# PCB.net
KiCad netlist of a schematic drawn in EAGLE
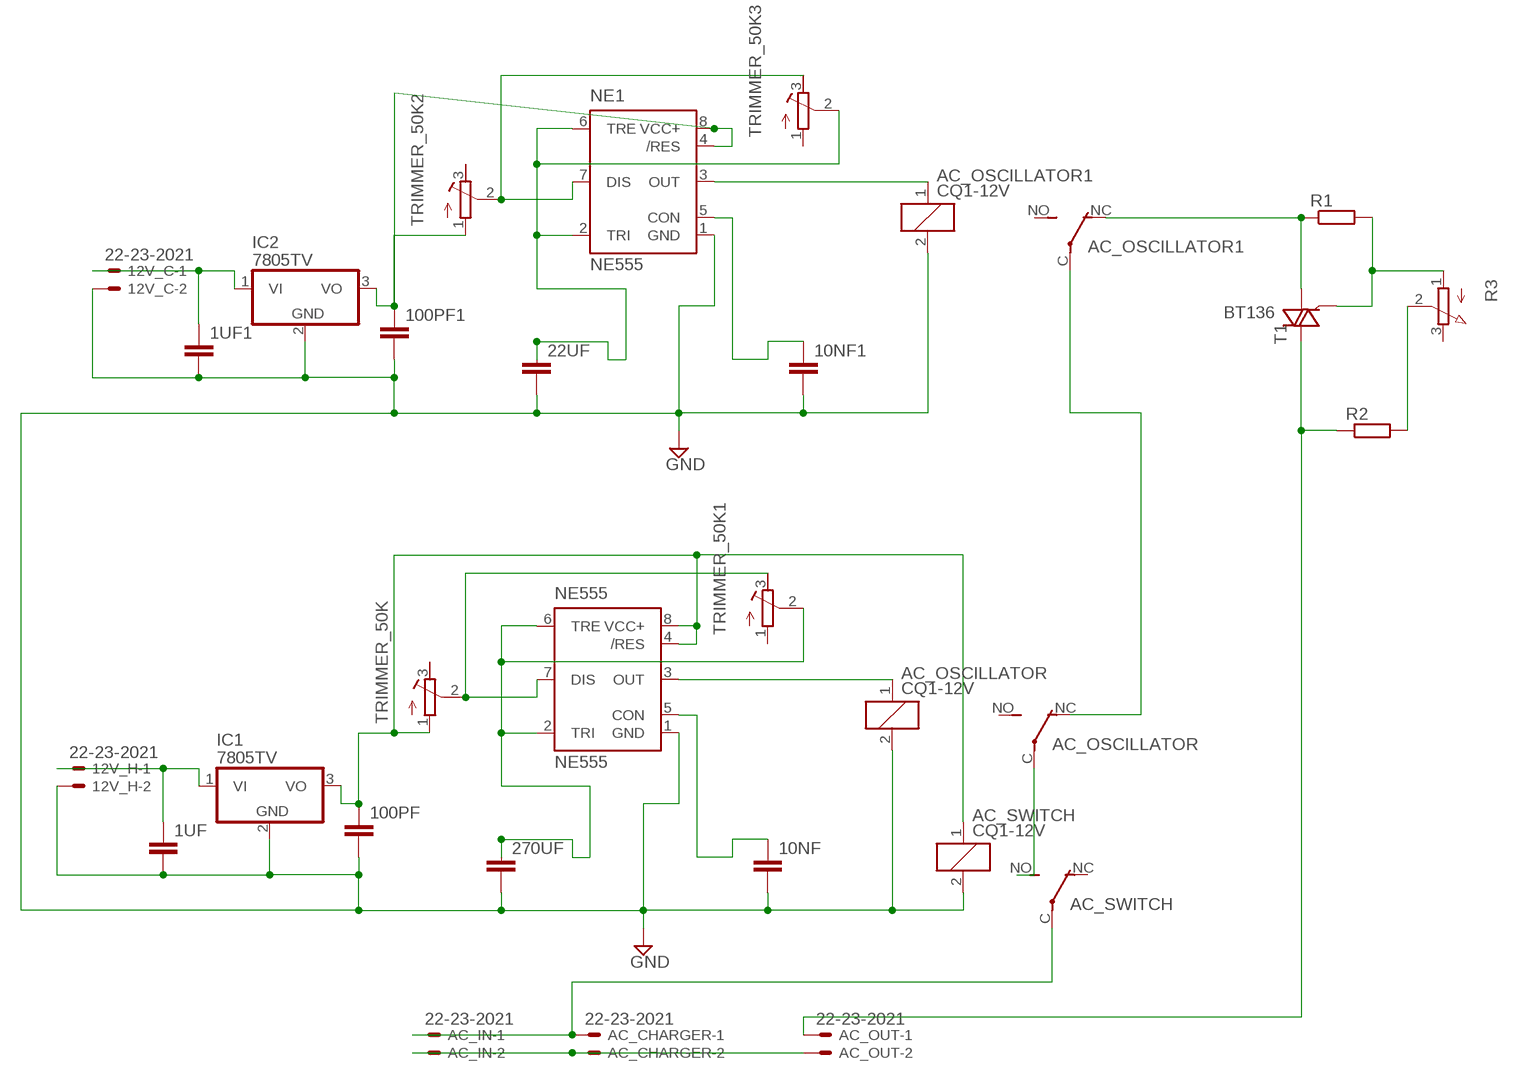
[diagram p0: schematic, sheet 1]

(export (version "E")
  (design (tool "Eeschema 10.0.6"))
  (components
    (comp (ref "1UF")
      (value "C7.5/3")
      (footprint "eagle-import:C7.5B3")
      (libsource (lib "eagle-import") (part "C7.5/3"))
    )
    (comp (ref "1UF1")
      (value "C7.5/3")
      (footprint "eagle-import:C7.5B3")
      (libsource (lib "eagle-import") (part "C7.5/3"))
    )
    (comp (ref "10NF")
      (value "C7.5/3")
      (footprint "eagle-import:C7.5B3")
      (libsource (lib "eagle-import") (part "C7.5/3"))
    )
    (comp (ref "10NF1")
      (value "C7.5/3")
      (footprint "eagle-import:C7.5B3")
      (libsource (lib "eagle-import") (part "C7.5/3"))
    )
    (comp (ref "12V_C")
      (value "22-23-2021")
      (footprint "eagle-import:22-23-2021")
      (fields (field (name "MF") "MOLEX"))
      (libsource (lib "eagle-import") (part "22-23-2021"))
    )
    (comp (ref "12V_H")
      (value "22-23-2021")
      (footprint "eagle-import:22-23-2021")
      (fields (field (name "MF") "MOLEX"))
      (libsource (lib "eagle-import") (part "22-23-2021"))
    )
    (comp (ref "22UF")
      (value "C7.5/3")
      (footprint "eagle-import:C7.5B3")
      (libsource (lib "eagle-import") (part "C7.5/3"))
    )
    (comp (ref "100PF")
      (value "C7.5/3")
      (footprint "eagle-import:C7.5B3")
      (libsource (lib "eagle-import") (part "C7.5/3"))
    )
    (comp (ref "100PF1")
      (value "C7.5/3")
      (footprint "eagle-import:C7.5B3")
      (libsource (lib "eagle-import") (part "C7.5/3"))
    )
    (comp (ref "270UF")
      (value "C7.5/3")
      (footprint "eagle-import:C7.5B3")
      (libsource (lib "eagle-import") (part "C7.5/3"))
    )
    (comp (ref "AC_CHARGER")
      (value "22-23-2021")
      (footprint "eagle-import:22-23-2021")
      (fields (field (name "MF") "MOLEX"))
      (libsource (lib "eagle-import") (part "22-23-2021"))
    )
    (comp (ref "AC_IN")
      (value "22-23-2021")
      (footprint "eagle-import:22-23-2021")
      (fields (field (name "MF") "MOLEX"))
      (libsource (lib "eagle-import") (part "22-23-2021"))
    )
    (comp (ref "AC_OSCILLATOR")
      (value "CQ1-12V")
      (footprint "eagle-import:CQ1")
      (libsource (lib "eagle-import") (part "CQ1-12V"))
    )
    (comp (ref "AC_OSCILLATOR1")
      (value "CQ1-12V")
      (footprint "eagle-import:CQ1")
      (libsource (lib "eagle-import") (part "CQ1-12V"))
    )
    (comp (ref "AC_OUT")
      (value "22-23-2021")
      (footprint "eagle-import:22-23-2021")
      (fields (field (name "MF") "MOLEX"))
      (libsource (lib "eagle-import") (part "22-23-2021"))
    )
    (comp (ref "AC_SWITCH")
      (value "CQ1-12V")
      (footprint "eagle-import:CQ1")
      (libsource (lib "eagle-import") (part "CQ1-12V"))
    )
    (comp (ref "IC1")
      (value "7805TV")
      (footprint "eagle-import:TO220V")
      (libsource (lib "eagle-import") (part "78TV05"))
    )
    (comp (ref "IC2")
      (value "7805TV")
      (footprint "eagle-import:TO220V")
      (libsource (lib "eagle-import") (part "78TV05"))
    )
    (comp (ref "NE1")
      (value "NE555")
      (footprint "eagle-import:DIL-08")
      (fields (field (name "MF") "Arrow Electronics") (field (name "MPN") "NE555N"))
      (libsource (lib "eagle-import") (part "NE555"))
    )
    (comp (ref "NE555")
      (value "NE555")
      (footprint "eagle-import:DIL-08")
      (fields (field (name "MF") "Arrow Electronics") (field (name "MPN") "NE555N"))
      (libsource (lib "eagle-import") (part "NE555"))
    )
    (comp (ref "R1")
      (value "R-EU_0204/7")
      (footprint "eagle-import:0204_7")
      (libsource (lib "eagle-import") (part "R-EU_0204/7"))
    )
    (comp (ref "R2")
      (value "R-EU_0204/7")
      (footprint "eagle-import:0204_7")
      (libsource (lib "eagle-import") (part "R-EU_0204/7"))
    )
    (comp (ref "R3")
      (value "3RP/1610N")
      (footprint "eagle-import:3RP_1610N")
      (libsource (lib "eagle-import") (part "3RP/1610N"))
    )
    (comp (ref "T1")
      (value "BT136")
      (footprint "eagle-import:TO220AB")
      (libsource (lib "eagle-import") (part "BT136"))
    )
    (comp (ref "TRIMMER_50K")
      (value "R-TRIMM64W")
      (footprint "eagle-import:RTRIM64W")
      (libsource (lib "eagle-import") (part "R-TRIMM64W"))
    )
    (comp (ref "TRIMMER_50K1")
      (value "R-TRIMM64W")
      (footprint "eagle-import:RTRIM64W")
      (libsource (lib "eagle-import") (part "R-TRIMM64W"))
    )
    (comp (ref "TRIMMER_50K2")
      (value "R-TRIMM64W")
      (footprint "eagle-import:RTRIM64W")
      (libsource (lib "eagle-import") (part "R-TRIMM64W"))
    )
    (comp (ref "TRIMMER_50K3")
      (value "R-TRIMM64W")
      (footprint "eagle-import:RTRIM64W")
      (libsource (lib "eagle-import") (part "R-TRIMM64W"))
    )
  )
  (nets
    (net (code "1") (name "GND") (class "Default")
      (node (ref "100PF") (pin "2") (pinfunction "2_2") (pintype "passive"))
      (node (ref "100PF1") (pin "2") (pinfunction "2_2") (pintype "passive"))
      (node (ref "10NF") (pin "2") (pinfunction "2_2") (pintype "passive"))
      (node (ref "10NF1") (pin "2") (pinfunction "2_2") (pintype "passive"))
      (node (ref "12V_C") (pin "2") (pinfunction "S_2") (pintype "passive"))
      (node (ref "12V_H") (pin "2") (pinfunction "S_2") (pintype "passive"))
      (node (ref "1UF") (pin "2") (pinfunction "2_2") (pintype "passive"))
      (node (ref "1UF1") (pin "2") (pinfunction "2_2") (pintype "passive"))
      (node (ref "22UF") (pin "2") (pinfunction "2_2") (pintype "passive"))
      (node (ref "270UF") (pin "2") (pinfunction "2_2") (pintype "passive"))
      (node (ref "AC_OSCILLATOR") (pin "2") (pinfunction "2_2") (pintype "passive"))
      (node (ref "AC_OSCILLATOR1") (pin "2") (pinfunction "2_2") (pintype "passive"))
      (node (ref "AC_SWITCH") (pin "2") (pinfunction "2_2") (pintype "passive"))
      (node (ref "IC1") (pin "2") (pinfunction "GND_2") (pintype "passive"))
      (node (ref "IC2") (pin "2") (pinfunction "GND_2") (pintype "passive"))
      (node (ref "NE1") (pin "1") (pinfunction "GND_1") (pintype "power_in"))
      (node (ref "NE555") (pin "1") (pinfunction "GND_1") (pintype "power_in"))
    )
    (net (code "2") (name "Net-(12V_CA-S)") (class "Default")
      (node (ref "12V_C") (pin "1") (pinfunction "S_1") (pintype "passive"))
      (node (ref "1UF1") (pin "1") (pinfunction "1_1") (pintype "passive"))
      (node (ref "IC2") (pin "1") (pinfunction "VI_1") (pintype "input"))
    )
    (net (code "3") (name "Net-(12V_HA-S)") (class "Default")
      (node (ref "12V_H") (pin "1") (pinfunction "S_1") (pintype "passive"))
      (node (ref "1UF") (pin "1") (pinfunction "1_1") (pintype "passive"))
      (node (ref "IC1") (pin "1") (pinfunction "VI_1") (pintype "input"))
    )
    (net (code "4") (name "Net-(AC_CHARGERA-S)") (class "Default")
      (node (ref "AC_CHARGER") (pin "1") (pinfunction "S_1") (pintype "passive"))
      (node (ref "AC_IN") (pin "1") (pinfunction "S_1") (pintype "passive"))
      (node (ref "AC_SWITCH") (pin "C") (pinfunction "P_C") (pintype "passive"))
    )
    (net (code "5") (name "Net-(AC_CHARGERB-S)") (class "Default")
      (node (ref "AC_CHARGER") (pin "2") (pinfunction "S_2") (pintype "passive"))
      (node (ref "AC_IN") (pin "2") (pinfunction "S_2") (pintype "passive"))
      (node (ref "AC_OUT") (pin "2") (pinfunction "S_2") (pintype "passive"))
    )
    (net (code "6") (name "Net-(AC_OSCILLATOR1B-O)") (class "Default")
      (node (ref "AC_OSCILLATOR1") (pin "NC") (pinfunction "O_NC") (pintype "passive"))
      (node (ref "R1") (pin "1") (pinfunction "1_1") (pintype "passive"))
      (node (ref "T1") (pin "1") (pinfunction "A1_1") (pintype "passive"))
    )
    (net (code "7") (name "Net-(AC_OSCILLATOR1B-P)") (class "Default")
      (node (ref "AC_OSCILLATOR") (pin "NC") (pinfunction "O_NC") (pintype "passive"))
      (node (ref "AC_OSCILLATOR1") (pin "C") (pinfunction "P_C") (pintype "passive"))
    )
    (net (code "8") (name "Net-(AC_OSCILLATORB-P)") (class "Default")
      (node (ref "AC_OSCILLATOR") (pin "C") (pinfunction "P_C") (pintype "passive"))
      (node (ref "AC_SWITCH") (pin "NO") (pinfunction "S_NO") (pintype "passive"))
    )
    (net (code "9") (name "Net-(AC_OUTA-S)") (class "Default")
      (node (ref "AC_OUT") (pin "1") (pinfunction "S_1") (pintype "passive"))
      (node (ref "R2") (pin "1") (pinfunction "1_1") (pintype "passive"))
      (node (ref "T1") (pin "2") (pinfunction "A2_2") (pintype "passive"))
    )
    (net (code "10") (name "Net-(IC1-VO)") (class "Default")
      (node (ref "100PF") (pin "1") (pinfunction "1_1") (pintype "passive"))
      (node (ref "AC_SWITCH") (pin "1") (pinfunction "1_1") (pintype "passive"))
      (node (ref "IC1") (pin "3") (pinfunction "VO_3") (pintype "passive"))
      (node (ref "NE555") (pin "4") (pinfunction "/RES_4") (pintype "input"))
      (node (ref "NE555") (pin "8") (pinfunction "VCC+_8") (pintype "power_in"))
      (node (ref "TRIMMER_50K") (pin "1") (pinfunction "A_1") (pintype "passive"))
    )
    (net (code "11") (name "Net-(IC2-VO)") (class "Default")
      (node (ref "100PF1") (pin "1") (pinfunction "1_1") (pintype "passive"))
      (node (ref "IC2") (pin "3") (pinfunction "VO_3") (pintype "passive"))
      (node (ref "NE1") (pin "4") (pinfunction "/RES_4") (pintype "input"))
      (node (ref "NE1") (pin "8") (pinfunction "VCC+_8") (pintype "power_in"))
      (node (ref "TRIMMER_50K2") (pin "1") (pinfunction "A_1") (pintype "passive"))
    )
    (net (code "12") (name "Net-(NE1-CON)") (class "Default")
      (node (ref "10NF1") (pin "1") (pinfunction "1_1") (pintype "passive"))
      (node (ref "NE1") (pin "5") (pinfunction "CON_5") (pintype "input"))
    )
    (net (code "13") (name "Net-(NE1-DIS)") (class "Default")
      (node (ref "NE1") (pin "7") (pinfunction "DIS_7") (pintype "input"))
      (node (ref "TRIMMER_50K2") (pin "2") (pinfunction "S_2") (pintype "passive"))
      (node (ref "TRIMMER_50K3") (pin "3") (pinfunction "E_3") (pintype "passive"))
    )
    (net (code "14") (name "Net-(NE1-OUT)") (class "Default")
      (node (ref "AC_OSCILLATOR1") (pin "1") (pinfunction "1_1") (pintype "passive"))
      (node (ref "NE1") (pin "3") (pinfunction "OUT_3") (pintype "output"))
    )
    (net (code "15") (name "Net-(NE1-TRE)") (class "Default")
      (node (ref "22UF") (pin "1") (pinfunction "1_1") (pintype "passive"))
      (node (ref "NE1") (pin "2") (pinfunction "TRI_2") (pintype "input"))
      (node (ref "NE1") (pin "6") (pinfunction "TRE_6") (pintype "input"))
      (node (ref "TRIMMER_50K3") (pin "2") (pinfunction "S_2") (pintype "passive"))
    )
    (net (code "16") (name "Net-(NE555-CON)") (class "Default")
      (node (ref "10NF") (pin "1") (pinfunction "1_1") (pintype "passive"))
      (node (ref "NE555") (pin "5") (pinfunction "CON_5") (pintype "input"))
    )
    (net (code "17") (name "Net-(NE555-DIS)") (class "Default")
      (node (ref "NE555") (pin "7") (pinfunction "DIS_7") (pintype "input"))
      (node (ref "TRIMMER_50K") (pin "2") (pinfunction "S_2") (pintype "passive"))
      (node (ref "TRIMMER_50K1") (pin "3") (pinfunction "E_3") (pintype "passive"))
    )
    (net (code "18") (name "Net-(NE555-OUT)") (class "Default")
      (node (ref "AC_OSCILLATOR") (pin "1") (pinfunction "1_1") (pintype "passive"))
      (node (ref "NE555") (pin "3") (pinfunction "OUT_3") (pintype "output"))
    )
    (net (code "19") (name "Net-(NE555-TRE)") (class "Default")
      (node (ref "270UF") (pin "1") (pinfunction "1_1") (pintype "passive"))
      (node (ref "NE555") (pin "2") (pinfunction "TRI_2") (pintype "input"))
      (node (ref "NE555") (pin "6") (pinfunction "TRE_6") (pintype "input"))
      (node (ref "TRIMMER_50K1") (pin "2") (pinfunction "S_2") (pintype "passive"))
    )
    (net (code "20") (name "Net-(R3-A)") (class "Default")
      (node (ref "R1") (pin "2") (pinfunction "2_2") (pintype "passive"))
      (node (ref "R3") (pin "1") (pinfunction "A_1") (pintype "passive"))
      (node (ref "T1") (pin "3") (pinfunction "G_3") (pintype "passive"))
    )
    (net (code "21") (name "Net-(R3-S)") (class "Default")
      (node (ref "R2") (pin "2") (pinfunction "2_2") (pintype "passive"))
      (node (ref "R3") (pin "2") (pinfunction "S_2") (pintype "passive"))
    )
    (net (code "22") (name "unconnected-(AC_OSCILLATOR1B-S-PadNO)") (class "Default")
      (node (ref "AC_OSCILLATOR1") (pin "NO") (pinfunction "S_NO") (pintype "passive"))
    )
    (net (code "23") (name "unconnected-(AC_OSCILLATORB-S-PadNO)") (class "Default")
      (node (ref "AC_OSCILLATOR") (pin "NO") (pinfunction "S_NO") (pintype "passive"))
    )
    (net (code "24") (name "unconnected-(AC_SWITCHB-O-PadNC)") (class "Default")
      (node (ref "AC_SWITCH") (pin "NC") (pinfunction "O_NC") (pintype "passive"))
    )
    (net (code "25") (name "unconnected-(R3-E-Pad3)") (class "Default")
      (node (ref "R3") (pin "3") (pinfunction "E_3") (pintype "passive"))
    )
    (net (code "26") (name "unconnected-(TRIMMER_50K-E-Pad3)") (class "Default")
      (node (ref "TRIMMER_50K") (pin "3") (pinfunction "E_3") (pintype "passive"))
    )
    (net (code "27") (name "unconnected-(TRIMMER_50K1-A-Pad1)") (class "Default")
      (node (ref "TRIMMER_50K1") (pin "1") (pinfunction "A_1") (pintype "passive"))
    )
    (net (code "28") (name "unconnected-(TRIMMER_50K2-E-Pad3)") (class "Default")
      (node (ref "TRIMMER_50K2") (pin "3") (pinfunction "E_3") (pintype "passive"))
    )
    (net (code "29") (name "unconnected-(TRIMMER_50K3-A-Pad1)") (class "Default")
      (node (ref "TRIMMER_50K3") (pin "1") (pinfunction "A_1") (pintype "passive"))
    )
  )
)
